# I2C_sensors.net
KiCad netlist of a schematic drawn in EAGLE
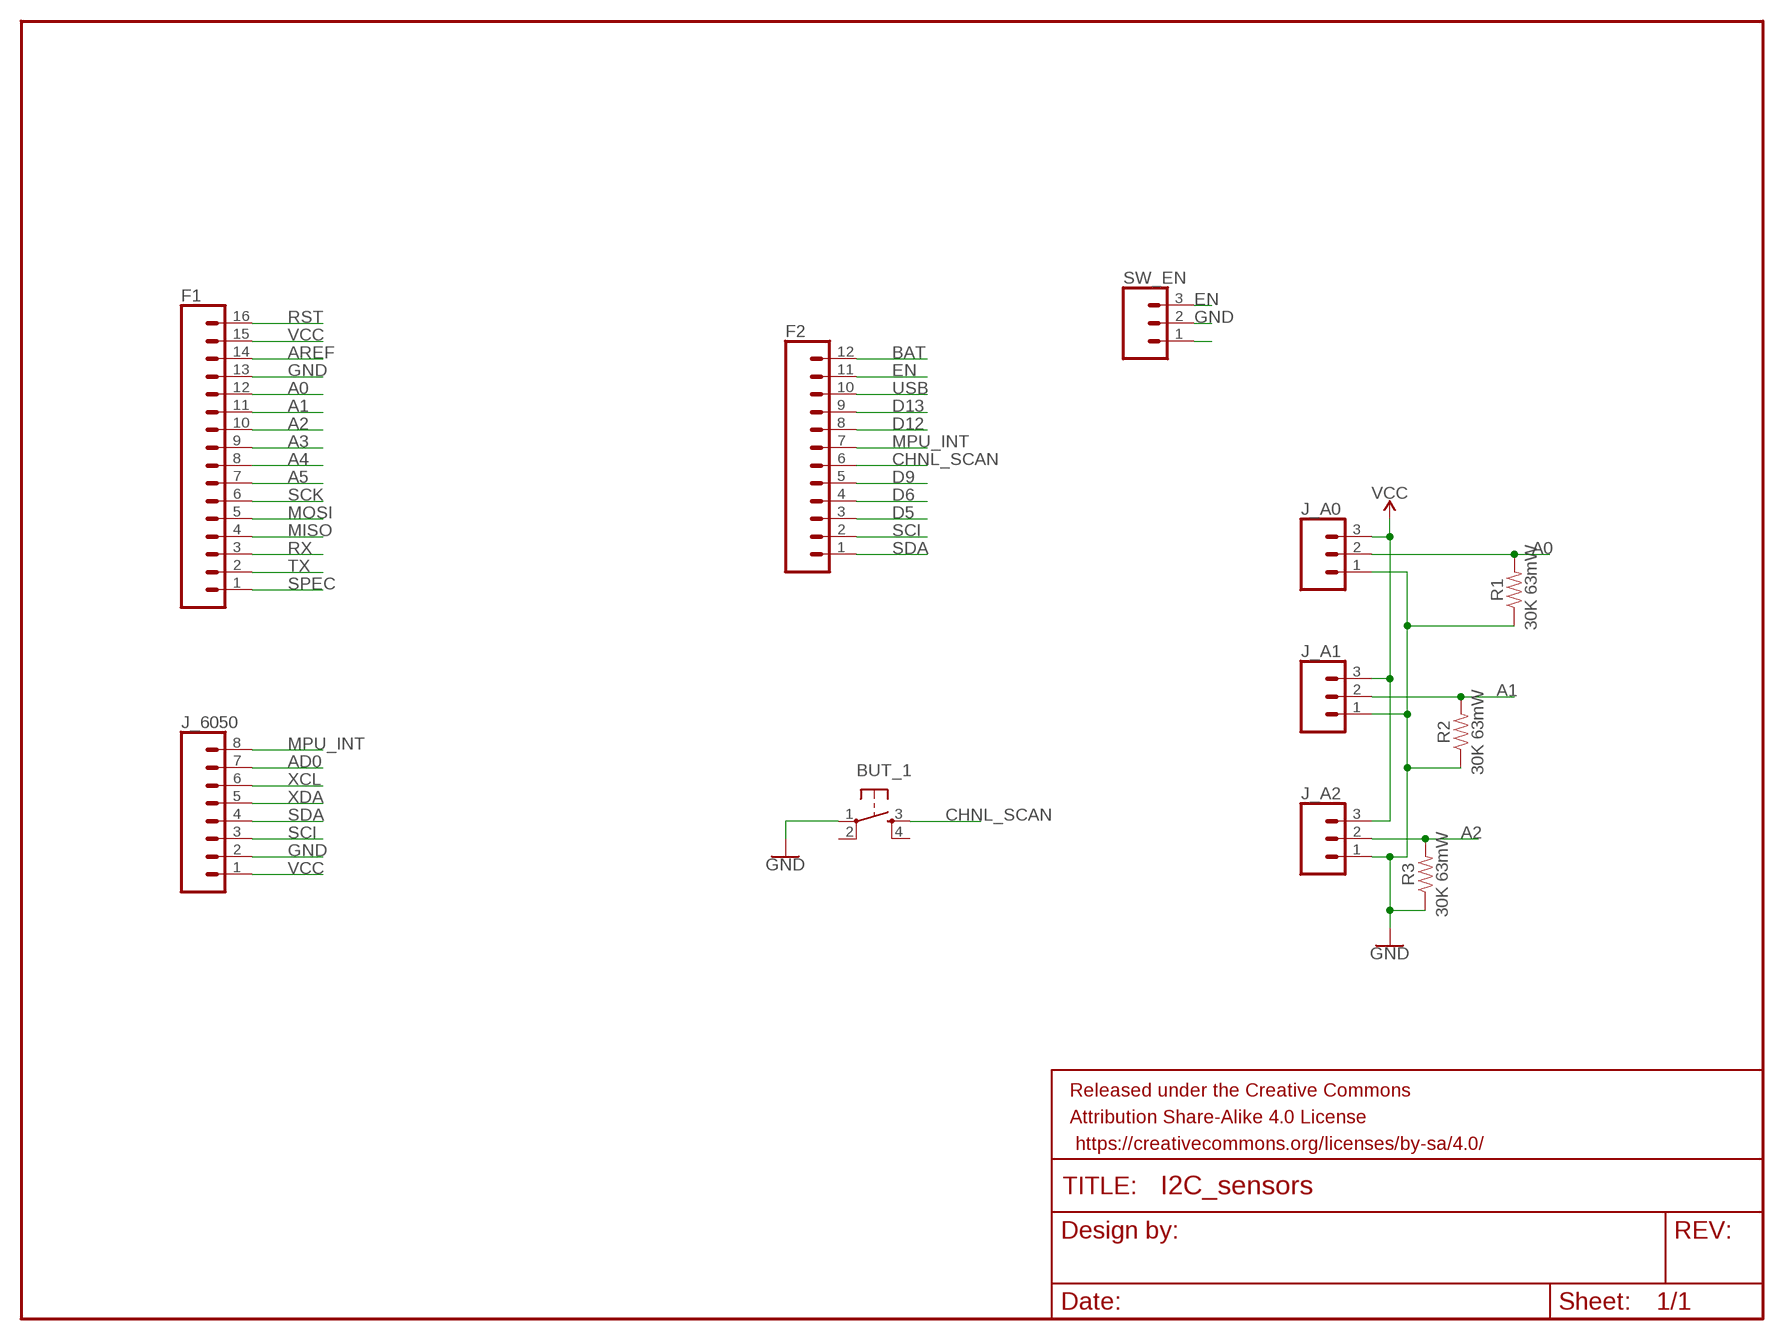
[diagram p0: schematic, sheet 1]

(export (version "E")
  (design (tool "Eeschema 10.0.6"))
  (components
    (comp (ref "BUT_1")
      (value "TAC_SWITCHPTH")
      (footprint "eagle-import:TACTILE-PTH")
      (libsource (lib "eagle-import") (part "TAC_SWITCHPTH"))
    )
    (comp (ref "F1")
      (value "CONN_16")
      (footprint "eagle-import:1X16")
      (libsource (lib "eagle-import") (part "CONN_16"))
    )
    (comp (ref "F2")
      (value "CONN_12")
      (footprint "eagle-import:1X12")
      (libsource (lib "eagle-import") (part "CONN_12"))
    )
    (comp (ref "FRAME1")
      (value "FRAME-LETTER")
      (footprint "eagle-import:CREATIVE_COMMONS")
      (libsource (lib "eagle-import") (part "FRAME-LETTER"))
    )
    (comp (ref "J_6050")
      (value "CONN_08\"")
      (footprint "eagle-import:1X08")
      (libsource (lib "eagle-import") (part "CONN_08{dblquote}"))
    )
    (comp (ref "J_A0")
      (value "CONN_03JST-PTH-VERT")
      (footprint "eagle-import:JST-3-PTH-VERT")
      (libsource (lib "eagle-import") (part "CONN_03JST-PTH-VERT"))
    )
    (comp (ref "J_A1")
      (value "CONN_03JST-PTH-VERT")
      (footprint "eagle-import:JST-3-PTH-VERT")
      (libsource (lib "eagle-import") (part "CONN_03JST-PTH-VERT"))
    )
    (comp (ref "J_A2")
      (value "CONN_03JST-PTH-VERT")
      (footprint "eagle-import:JST-3-PTH-VERT")
      (libsource (lib "eagle-import") (part "CONN_03JST-PTH-VERT"))
    )
    (comp (ref "R1")
      (value "30K 63mW")
      (footprint "eagle-import:0805")
      (libsource (lib "eagle-import") (part "RESISTOR0805"))
    )
    (comp (ref "R2")
      (value "30K 63mW")
      (footprint "eagle-import:0805")
      (libsource (lib "eagle-import") (part "RESISTOR0805"))
    )
    (comp (ref "R3")
      (value "30K 63mW")
      (footprint "eagle-import:0805")
      (libsource (lib "eagle-import") (part "RESISTOR0805"))
    )
    (comp (ref "SW_EN")
      (value "CONN_03")
      (footprint "eagle-import:1X03")
      (libsource (lib "eagle-import") (part "CONN_03"))
    )
  )
  (nets
    (net (code "1") (name "/A0") (class "Default")
      (node (ref "F1") (pin "12") (pinfunction "12_12") (pintype "passive"))
      (node (ref "J_A0") (pin "2") (pinfunction "2_2") (pintype "passive"))
      (node (ref "R1") (pin "2") (pinfunction "2_2") (pintype "passive"))
    )
    (net (code "2") (name "/A1") (class "Default")
      (node (ref "F1") (pin "11") (pinfunction "11_11") (pintype "passive"))
      (node (ref "J_A1") (pin "2") (pinfunction "2_2") (pintype "passive"))
      (node (ref "R2") (pin "2") (pinfunction "2_2") (pintype "passive"))
    )
    (net (code "3") (name "/A2") (class "Default")
      (node (ref "F1") (pin "10") (pinfunction "10_10") (pintype "passive"))
      (node (ref "J_A2") (pin "2") (pinfunction "2_2") (pintype "passive"))
      (node (ref "R3") (pin "2") (pinfunction "2_2") (pintype "passive"))
    )
    (net (code "4") (name "/A3") (class "Default")
      (node (ref "F1") (pin "9") (pinfunction "9_9") (pintype "passive"))
    )
    (net (code "5") (name "/A4") (class "Default")
      (node (ref "F1") (pin "8") (pinfunction "8_8") (pintype "passive"))
    )
    (net (code "6") (name "/A5") (class "Default")
      (node (ref "F1") (pin "7") (pinfunction "7_7") (pintype "passive"))
    )
    (net (code "7") (name "/AD0") (class "Default")
      (node (ref "J_6050") (pin "7") (pinfunction "7_7") (pintype "passive"))
    )
    (net (code "8") (name "/AREF") (class "Default")
      (node (ref "F1") (pin "14") (pinfunction "14_14") (pintype "passive"))
    )
    (net (code "9") (name "/BAT") (class "Default")
      (node (ref "F2") (pin "12") (pinfunction "12_12") (pintype "passive"))
    )
    (net (code "10") (name "/CHNL_SCAN") (class "Default")
      (node (ref "BUT_1") (pin "3") (pinfunction "3_3") (pintype "passive"))
      (node (ref "F2") (pin "6") (pinfunction "6_6") (pintype "passive"))
    )
    (net (code "11") (name "/D5") (class "Default")
      (node (ref "F2") (pin "3") (pinfunction "3_3") (pintype "passive"))
    )
    (net (code "12") (name "/D6") (class "Default")
      (node (ref "F2") (pin "4") (pinfunction "4_4") (pintype "passive"))
    )
    (net (code "13") (name "/D9") (class "Default")
      (node (ref "F2") (pin "5") (pinfunction "5_5") (pintype "passive"))
    )
    (net (code "14") (name "/D12") (class "Default")
      (node (ref "F2") (pin "8") (pinfunction "8_8") (pintype "passive"))
    )
    (net (code "15") (name "/D13") (class "Default")
      (node (ref "F2") (pin "9") (pinfunction "9_9") (pintype "passive"))
    )
    (net (code "16") (name "/EN") (class "Default")
      (node (ref "F2") (pin "11") (pinfunction "11_11") (pintype "passive"))
      (node (ref "SW_EN") (pin "3") (pinfunction "3_3") (pintype "passive"))
    )
    (net (code "17") (name "/MISO") (class "Default")
      (node (ref "F1") (pin "4") (pinfunction "4_4") (pintype "passive"))
    )
    (net (code "18") (name "/MOSI") (class "Default")
      (node (ref "F1") (pin "5") (pinfunction "5_5") (pintype "passive"))
    )
    (net (code "19") (name "/MPU_INT") (class "Default")
      (node (ref "F2") (pin "7") (pinfunction "7_7") (pintype "passive"))
      (node (ref "J_6050") (pin "8") (pinfunction "8_8") (pintype "passive"))
    )
    (net (code "20") (name "/RST") (class "Default")
      (node (ref "F1") (pin "16") (pinfunction "16_16") (pintype "passive"))
    )
    (net (code "21") (name "/RX") (class "Default")
      (node (ref "F1") (pin "3") (pinfunction "3_3") (pintype "passive"))
    )
    (net (code "22") (name "/SCI") (class "Default")
      (node (ref "F2") (pin "2") (pinfunction "2_2") (pintype "passive"))
      (node (ref "J_6050") (pin "3") (pinfunction "3_3") (pintype "passive"))
    )
    (net (code "23") (name "/SCK") (class "Default")
      (node (ref "F1") (pin "6") (pinfunction "6_6") (pintype "passive"))
    )
    (net (code "24") (name "/SDA") (class "Default")
      (node (ref "F2") (pin "1") (pinfunction "1_1") (pintype "passive"))
      (node (ref "J_6050") (pin "4") (pinfunction "4_4") (pintype "passive"))
    )
    (net (code "25") (name "/SPEC") (class "Default")
      (node (ref "F1") (pin "1") (pinfunction "1_1") (pintype "passive"))
    )
    (net (code "26") (name "/TX") (class "Default")
      (node (ref "F1") (pin "2") (pinfunction "2_2") (pintype "passive"))
    )
    (net (code "27") (name "/USB") (class "Default")
      (node (ref "F2") (pin "10") (pinfunction "10_10") (pintype "passive"))
    )
    (net (code "28") (name "/XCL") (class "Default")
      (node (ref "J_6050") (pin "6") (pinfunction "6_6") (pintype "passive"))
    )
    (net (code "29") (name "/XDA") (class "Default")
      (node (ref "J_6050") (pin "5") (pinfunction "5_5") (pintype "passive"))
    )
    (net (code "30") (name "GND") (class "Default")
      (node (ref "BUT_1") (pin "1") (pinfunction "1_1") (pintype "passive"))
      (node (ref "F1") (pin "13") (pinfunction "13_13") (pintype "passive"))
      (node (ref "J_6050") (pin "2") (pinfunction "2_2") (pintype "passive"))
      (node (ref "J_A0") (pin "1") (pinfunction "1_1") (pintype "passive"))
      (node (ref "J_A1") (pin "1") (pinfunction "1_1") (pintype "passive"))
      (node (ref "J_A2") (pin "1") (pinfunction "1_1") (pintype "passive"))
      (node (ref "R1") (pin "1") (pinfunction "1_1") (pintype "passive"))
      (node (ref "R2") (pin "1") (pinfunction "1_1") (pintype "passive"))
      (node (ref "R3") (pin "1") (pinfunction "1_1") (pintype "passive"))
      (node (ref "SW_EN") (pin "2") (pinfunction "2_2") (pintype "passive"))
    )
    (net (code "31") (name "VCC") (class "Default")
      (node (ref "F1") (pin "15") (pinfunction "15_15") (pintype "passive"))
      (node (ref "J_6050") (pin "1") (pinfunction "1_1") (pintype "passive"))
      (node (ref "J_A0") (pin "3") (pinfunction "3_3") (pintype "passive"))
      (node (ref "J_A1") (pin "3") (pinfunction "3_3") (pintype "passive"))
      (node (ref "J_A2") (pin "3") (pinfunction "3_3") (pintype "passive"))
    )
    (net (code "32") (name "unconnected-(BUT_1-Pad2)") (class "Default")
      (node (ref "BUT_1") (pin "2") (pinfunction "2_2") (pintype "passive"))
    )
    (net (code "33") (name "unconnected-(BUT_1-Pad4)") (class "Default")
      (node (ref "BUT_1") (pin "4") (pinfunction "4_4") (pintype "passive"))
    )
    (net (code "34") (name "unconnected-(SW_EN-Pad1)") (class "Default")
      (node (ref "SW_EN") (pin "1") (pinfunction "1_1") (pintype "passive"))
    )
  )
)
